# DeejBusinessCard-Top.net
KiCad netlist of a schematic drawn in Altium Designer
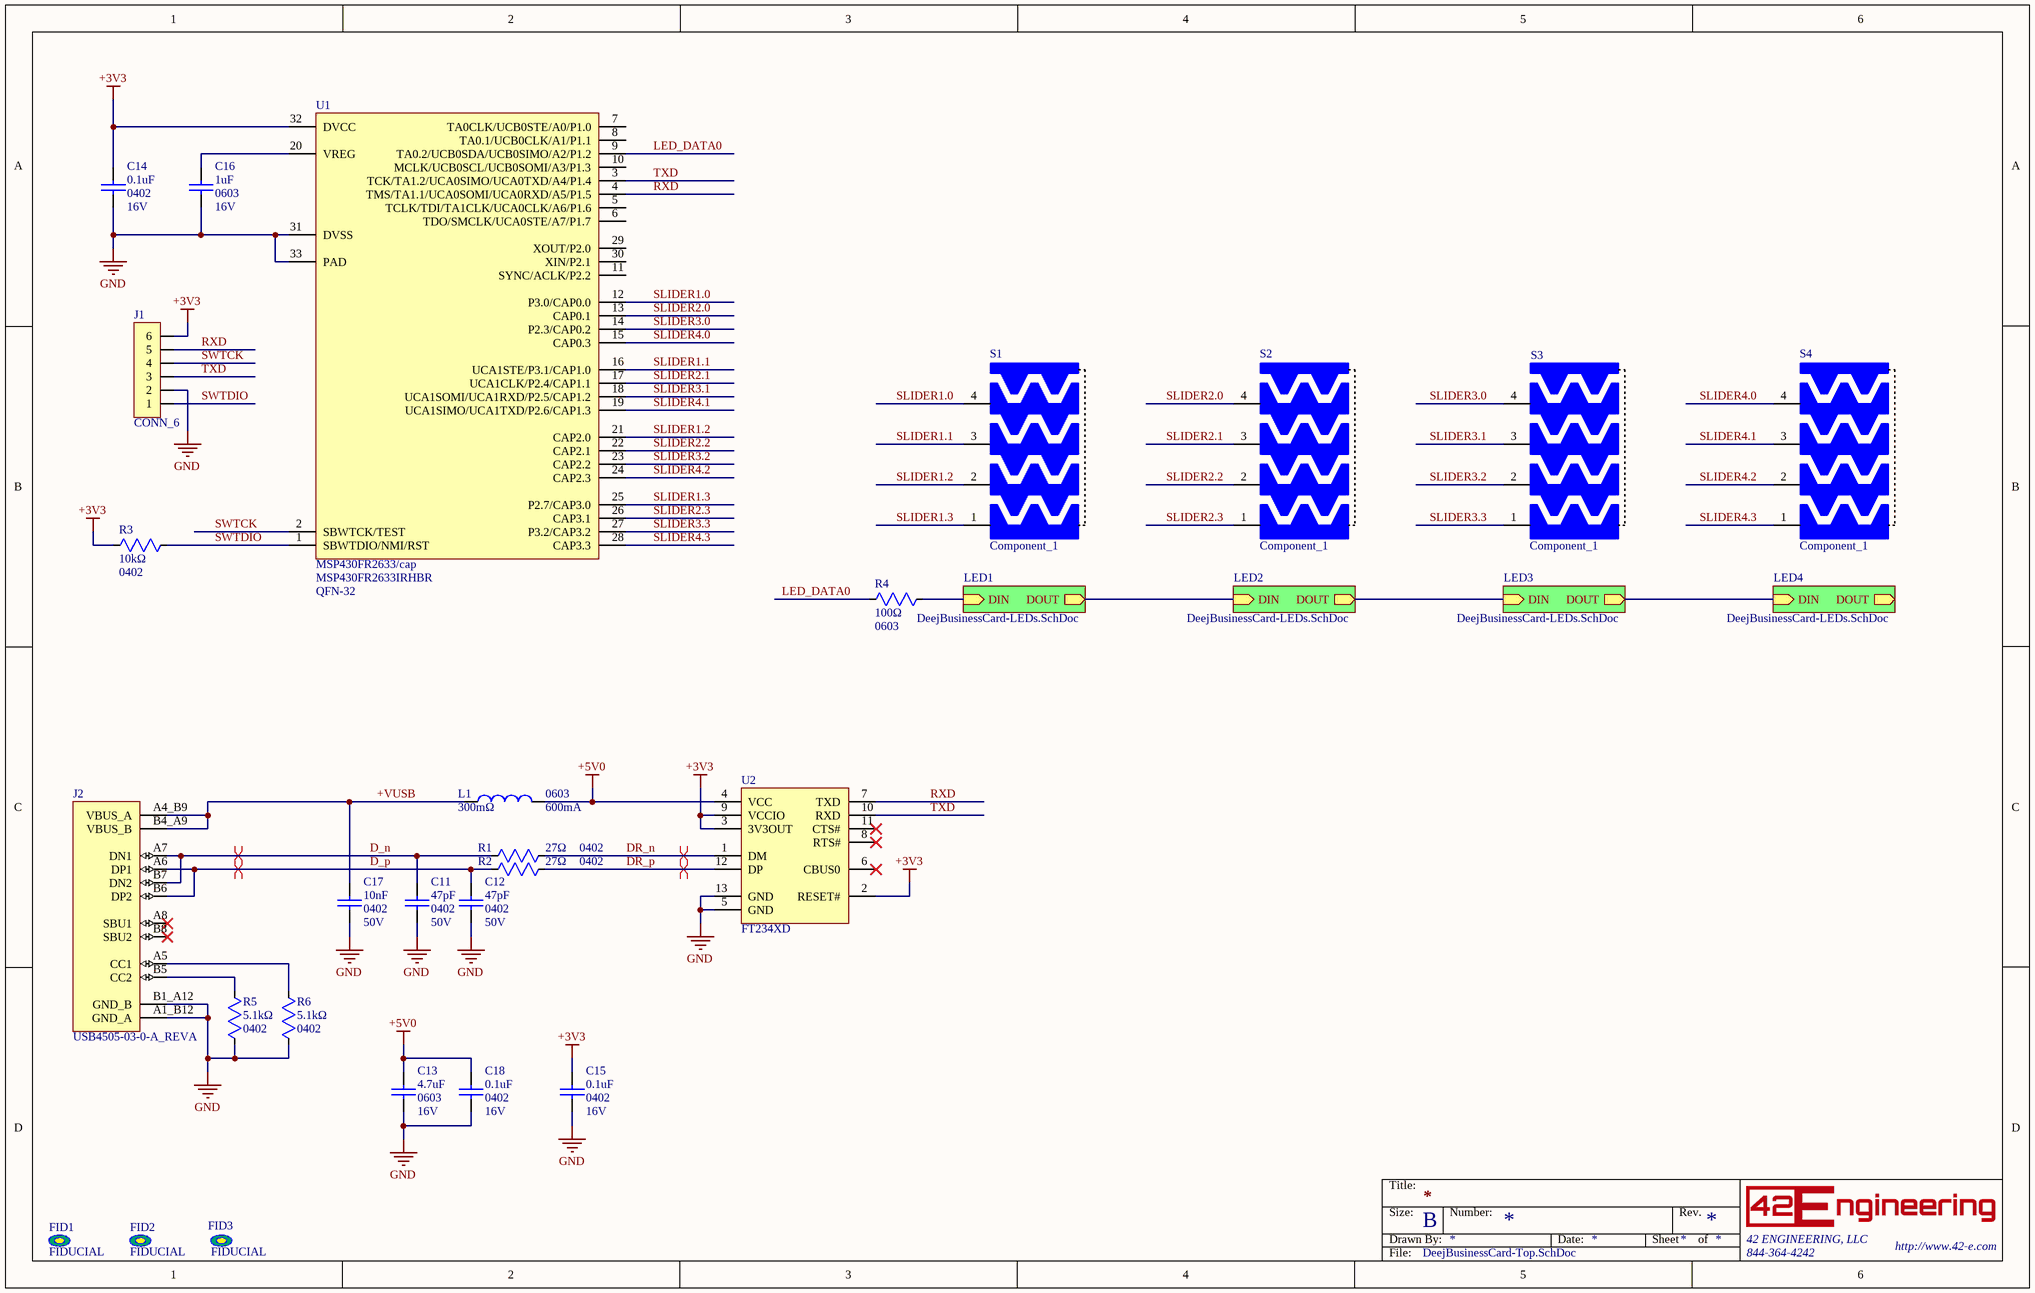
[diagram p0: DeejBusinessCard-Top.SchDoc]

(export (version "E")
  (design (tool "Eeschema 10.0.6"))
  (components
    (comp (ref "C11")
      (value "47pF")
      (footprint "CAPC1005L")
      (description "CAP CER 47PF 50V C0G/NP0 0402")
      (fields
        (field (name "CASE/PACKAGE") "0402")
        (field (name "VOLTAGE") "50V")
        (field (name "PART NUMBER") "CL05C470JB5NNNC")
        (field (name "Comment") "Capacitor_Ceramic")
      )
      (libsource (lib "Capacitors") (part "Capacitor_Ceramic"))
    )
    (comp (ref "C12")
      (value "47pF")
      (footprint "CAPC1005L")
      (description "CAP CER 47PF 50V C0G/NP0 0402")
      (fields
        (field (name "CASE/PACKAGE") "0402")
        (field (name "VOLTAGE") "50V")
        (field (name "PART NUMBER") "CL05C470JB5NNNC")
        (field (name "Comment") "Capacitor_Ceramic")
      )
      (libsource (lib "Capacitors") (part "Capacitor_Ceramic"))
    )
    (comp (ref "C13")
      (value "4.7uF")
      (footprint "CAPC1608N")
      (description "CAP CER 4.7UF 16V X7R 0603")
      (fields
        (field (name "CASE/PACKAGE") "0603")
        (field (name "VOLTAGE") "16V")
        (field (name "PART NUMBER") "GRM188Z71C475KE21J")
        (field (name "Comment") "Capacitor_Ceramic")
      )
      (libsource (lib "Capacitors") (part "Capacitor_Ceramic"))
    )
    (comp (ref "C14")
      (value "0.1uF")
      (footprint "CAPC1005L")
      (description "CAP CER 0.1UF 16V X7R 0402")
      (fields
        (field (name "CASE/PACKAGE") "0402")
        (field (name "VOLTAGE") "16V")
        (field (name "PART NUMBER") "CC0402KRX7R7BB104")
        (field (name "Comment") "Capacitor_Ceramic")
      )
      (libsource (lib "Capacitors") (part "Capacitor_Ceramic"))
    )
    (comp (ref "C15")
      (value "0.1uF")
      (footprint "CAPC1005L")
      (description "CAP CER 0.1UF 16V X7R 0402")
      (fields
        (field (name "CASE/PACKAGE") "0402")
        (field (name "VOLTAGE") "16V")
        (field (name "PART NUMBER") "CC0402KRX7R7BB104")
        (field (name "Comment") "Capacitor_Ceramic")
      )
      (libsource (lib "Capacitors") (part "Capacitor_Ceramic"))
    )
    (comp (ref "C16")
      (value "1uF")
      (footprint "CAPC1608N")
      (description "CAP CER 1UF 16V X7R 0603")
      (fields
        (field (name "CASE/PACKAGE") "0603")
        (field (name "VOLTAGE") "16V")
        (field (name "PART NUMBER") "CC0603JRX7R7BB105")
        (field (name "Comment") "Capacitor_Ceramic")
      )
      (libsource (lib "Capacitors") (part "Capacitor_Ceramic"))
    )
    (comp (ref "C17")
      (value "10nF")
      (footprint "CAPC1005L")
      (description "CAP CER 10000PF 50V X7R 0402")
      (fields
        (field (name "CASE/PACKAGE") "0402")
        (field (name "VOLTAGE") "50V")
        (field (name "PART NUMBER") "CC0402JRX7R9BB103")
        (field (name "Comment") "Capacitor_Ceramic")
      )
      (libsource (lib "Capacitors") (part "Capacitor_Ceramic"))
    )
    (comp (ref "C18")
      (value "0.1uF")
      (footprint "CAPC1005L")
      (description "CAP CER 0.1UF 16V X7R 0402")
      (fields
        (field (name "CASE/PACKAGE") "0402")
        (field (name "VOLTAGE") "16V")
        (field (name "PART NUMBER") "CC0402KRX7R7BB104")
        (field (name "Comment") "Capacitor_Ceramic")
      )
      (libsource (lib "Capacitors") (part "Capacitor_Ceramic"))
    )
    (comp (ref "FID1")
      (value "FIDUCIAL")
      (footprint "FIDUCIAL_1mm")
      (description "1MM Fiducial")
      (libsource (lib "42e-SharedLib") (part "FIDUCIAL"))
    )
    (comp (ref "FID2")
      (value "FIDUCIAL")
      (footprint "FIDUCIAL_1mm")
      (description "1MM Fiducial")
      (libsource (lib "42e-SharedLib") (part "FIDUCIAL"))
    )
    (comp (ref "FID3")
      (value "FIDUCIAL")
      (footprint "FIDUCIAL_1mm")
      (description "1MM Fiducial")
      (libsource (lib "42e-SharedLib") (part "FIDUCIAL"))
    )
    (comp (ref "J1")
      (value "CONN_6")
      (footprint "HDR - TC2030-IDC-NL-FP")
      (fields (field (name "PART NUMBER") "Header GENERIC 6pin POGO"))
      (libsource (lib "Mechanical_Other") (part "CONN_6"))
    )
    (comp (ref "J2")
      (value "USB4505-03-0-A_REVA")
      (footprint "GCT_USB4505-03-0-A_REVA")
      (fields (field (name "MP") "USB4505-03-0-A") (field (name "MF") "Global Connector Technology"))
      (libsource (lib "USB4505-03-0-A_REVA") (part "USB4505-03-0-A_REVA"))
    )
    (comp (ref "L1")
      (value "300mΩ")
      (footprint "RESC1608N")
      (description "FERRITE BEAD 1K OHM 0603 1LN")
      (fields
        (field (name "PART NUMBER") "742792662")
        (field (name "CASE/PACKAGE") "0603")
        (field (name "CURRENT") "600mA")
        (field (name "Comment") "Inductor")
      )
      (libsource (lib "Inductors") (part "Inductor"))
    )
    (comp (ref "R1")
      (value "27Ω")
      (footprint "RESC1005L")
      (description "Resistor, 27Ω, 1%, 0.05W, 0402")
      (fields
        (field (name "CASE/PACKAGE") "0402")
        (field (name "PART NUMBER") "RES0402F27R0")
        (field (name "Comment") "Resistor")
      )
      (libsource (lib "Resistors") (part "Resistor"))
    )
    (comp (ref "R2")
      (value "27Ω")
      (footprint "RESC1005L")
      (description "Resistor, 27Ω, 1%, 0.05W, 0402")
      (fields
        (field (name "CASE/PACKAGE") "0402")
        (field (name "PART NUMBER") "RES0402F27R0")
        (field (name "Comment") "Resistor")
      )
      (libsource (lib "Resistors") (part "Resistor"))
    )
    (comp (ref "R3")
      (value "10kΩ")
      (footprint "RESC1005L")
      (description "Resistor, 10kΩ, 1%, 0.05W, 0402")
      (fields
        (field (name "CASE/PACKAGE") "0402")
        (field (name "PART NUMBER") "RES0402F10K0")
        (field (name "Comment") "Resistor")
      )
      (libsource (lib "Resistors") (part "Resistor"))
    )
    (comp (ref "R4")
      (value "100Ω")
      (footprint "RESC1608N")
      (description "Resistor, 100Ω, 1%, 0.1W, 0603")
      (fields
        (field (name "CASE/PACKAGE") "0603")
        (field (name "PART NUMBER") "RES0603F100R")
        (field (name "Comment") "Resistor")
      )
      (libsource (lib "Resistors") (part "Resistor"))
    )
    (comp (ref "R5")
      (value "5.1kΩ")
      (footprint "RESC1005L")
      (description "Resistor, 5.1kΩ, 1%, 0.05W, 0402")
      (fields
        (field (name "CASE/PACKAGE") "0402")
        (field (name "PART NUMBER") "RES0402F5K10")
        (field (name "Comment") "Resistor")
      )
      (libsource (lib "Resistors") (part "Resistor"))
    )
    (comp (ref "R6")
      (value "5.1kΩ")
      (footprint "RESC1005L")
      (description "Resistor, 5.1kΩ, 1%, 0.05W, 0402")
      (fields
        (field (name "CASE/PACKAGE") "0402")
        (field (name "PART NUMBER") "RES0402F5K10")
        (field (name "Comment") "Resistor")
      )
      (libsource (lib "Resistors") (part "Resistor"))
    )
    (comp (ref "S1")
      (value "Component_1")
      (footprint "SLIDER-4-38-13")
      (libsource (lib "Schlib1") (part "Component_1"))
    )
    (comp (ref "S2")
      (value "Component_1")
      (footprint "SLIDER-4-38-13")
      (libsource (lib "Schlib1") (part "Component_1"))
    )
    (comp (ref "S3")
      (value "Component_1")
      (footprint "SLIDER-4-38-13")
      (libsource (lib "Schlib1") (part "Component_1"))
    )
    (comp (ref "S4")
      (value "Component_1")
      (footprint "SLIDER-4-38-13")
      (libsource (lib "Schlib1") (part "Component_1"))
    )
    (comp (ref "U1")
      (value "MSP430FR2633/cap")
      (footprint "QFN50P500X500X100_HS-33N")
      (description "IC MCU 16BIT 15.5KB FRAM 32VQFN")
      (fields
        (field (name "PART NUMBER") "MSP430FR2633")
        (field (name "MANUFACTURER PART NUMBER 1") "MSP430FR2633IRHBR")
        (field (name "CASE/PACKAGE") "QFN-32")
      )
      (libsource (lib "ICs") (part "MSP430FR2633/cap"))
    )
    (comp (ref "U2")
      (value "FT234XD")
      (footprint "SON45P300X80_HS-13N")
      (description "IC USB SERIAL BASIC UART 12DFN")
      (libsource (lib "UEC Shared Schematic Library") (part "FT234XD"))
    )
  )
  (nets
    (net (code "1") (name "+3V3") (class "Default")
      (node (ref "C14") (pin "1") (pinfunction "1_1") (pintype "passive"))
      (node (ref "C15") (pin "1") (pinfunction "1_1") (pintype "passive"))
      (node (ref "J1") (pin "6") (pinfunction "6_6") (pintype "passive"))
      (node (ref "R3") (pin "2") (pintype "passive"))
      (node (ref "U1") (pin "32") (pinfunction "DVCC_32") (pintype "passive"))
      (node (ref "U2") (pin "2") (pinfunction "RESET#_2") (pintype "passive"))
      (node (ref "U2") (pin "3") (pinfunction "3V3OUT_3") (pintype "passive"))
      (node (ref "U2") (pin "9") (pinfunction "VCCIO_9") (pintype "passive"))
    )
    (net (code "2") (name "+5V0") (class "Default")
      (node (ref "C13") (pin "2") (pinfunction "2_2") (pintype "passive"))
      (node (ref "C18") (pin "1") (pinfunction "1_1") (pintype "passive"))
      (node (ref "L1") (pin "2") (pinfunction "Pri-_2") (pintype "passive"))
      (node (ref "U2") (pin "4") (pinfunction "VCC_4") (pintype "passive"))
    )
    (net (code "3") (name "/+VUSB") (class "Default")
      (node (ref "C17") (pin "2") (pinfunction "2_2") (pintype "passive"))
      (node (ref "J2") (pin "A4_B9") (pinfunction "VBUS_A_A4_B9") (pintype "power_in"))
      (node (ref "J2") (pin "B4_A9") (pinfunction "VBUS_B_B4_A9") (pintype "power_in"))
      (node (ref "L1") (pin "1") (pinfunction "Pri+_1") (pintype "passive"))
    )
    (net (code "4") (name "/DIN") (class "Default") (node (ref "R4") (pin "2") (pintype "passive")))
    (net (code "9") (name "/DR_n") (class "Default")
      (node (ref "R1") (pin "2") (pintype "passive"))
      (node (ref "U2") (pin "1") (pinfunction "DM_1") (pintype "passive"))
    )
    (net (code "10") (name "/DR_p") (class "Default")
      (node (ref "R2") (pin "2") (pintype "passive"))
      (node (ref "U2") (pin "12") (pinfunction "DP_12") (pintype "passive"))
    )
    (net (code "11") (name "/D_n") (class "Default")
      (node (ref "C11") (pin "2") (pinfunction "2_2") (pintype "passive"))
      (node (ref "J2") (pin "A7") (pinfunction "DN1_A7") (pintype "bidirectional"))
      (node (ref "J2") (pin "B7") (pinfunction "DN2_B7") (pintype "bidirectional"))
      (node (ref "R1") (pin "1") (pintype "passive"))
    )
    (net (code "12") (name "/D_p") (class "Default")
      (node (ref "C12") (pin "2") (pinfunction "2_2") (pintype "passive"))
      (node (ref "J2") (pin "A6") (pinfunction "DP1_A6") (pintype "bidirectional"))
      (node (ref "J2") (pin "B6") (pinfunction "DP2_B6") (pintype "bidirectional"))
      (node (ref "R2") (pin "1") (pintype "passive"))
    )
    (net (code "13") (name "/LED_DATA0") (class "Default")
      (node (ref "R4") (pin "1") (pintype "passive"))
      (node (ref "U1") (pin "9") (pinfunction "TA0.2/UCB0SDA/UCB0SIMO/A2/P1.2_9") (pintype "passive"))
    )
    (net (code "14") (name "/RXD") (class "Default")
      (node (ref "J1") (pin "5") (pinfunction "5_5") (pintype "passive"))
      (node (ref "U1") (pin "4") (pinfunction "TMS/TA1.1/UCA0SOMI/UCA0RXD/A5/P1.5_4") (pintype "passive"))
      (node (ref "U2") (pin "7") (pinfunction "TXD_7") (pintype "passive"))
    )
    (net (code "15") (name "/SLIDER1.0") (class "Default")
      (node (ref "S1") (pin "4") (pinfunction "4_4") (pintype "passive"))
      (node (ref "U1") (pin "12") (pinfunction "P3.0/CAP0.0_12") (pintype "passive"))
    )
    (net (code "16") (name "/SLIDER1.1") (class "Default")
      (node (ref "S1") (pin "3") (pinfunction "3_3") (pintype "passive"))
      (node (ref "U1") (pin "16") (pinfunction "UCA1STE/P3.1/CAP1.0_16") (pintype "passive"))
    )
    (net (code "17") (name "/SLIDER1.2") (class "Default")
      (node (ref "S1") (pin "2") (pinfunction "2_2") (pintype "passive"))
      (node (ref "U1") (pin "21") (pinfunction "CAP2.0_21") (pintype "passive"))
    )
    (net (code "18") (name "/SLIDER1.3") (class "Default")
      (node (ref "S1") (pin "1") (pinfunction "1_1") (pintype "passive"))
      (node (ref "U1") (pin "25") (pinfunction "P2.7/CAP3.0_25") (pintype "passive"))
    )
    (net (code "19") (name "/SLIDER2.0") (class "Default")
      (node (ref "S2") (pin "4") (pinfunction "4_4") (pintype "passive"))
      (node (ref "U1") (pin "13") (pinfunction "CAP0.1_13") (pintype "passive"))
    )
    (net (code "20") (name "/SLIDER2.1") (class "Default")
      (node (ref "S2") (pin "3") (pinfunction "3_3") (pintype "passive"))
      (node (ref "U1") (pin "17") (pinfunction "UCA1CLK/P2.4/CAP1.1_17") (pintype "passive"))
    )
    (net (code "21") (name "/SLIDER2.2") (class "Default")
      (node (ref "S2") (pin "2") (pinfunction "2_2") (pintype "passive"))
      (node (ref "U1") (pin "22") (pinfunction "CAP2.1_22") (pintype "passive"))
    )
    (net (code "22") (name "/SLIDER2.3") (class "Default")
      (node (ref "S2") (pin "1") (pinfunction "1_1") (pintype "passive"))
      (node (ref "U1") (pin "26") (pinfunction "CAP3.1_26") (pintype "passive"))
    )
    (net (code "23") (name "/SLIDER3.0") (class "Default")
      (node (ref "S3") (pin "4") (pinfunction "4_4") (pintype "passive"))
      (node (ref "U1") (pin "14") (pinfunction "P2.3/CAP0.2_14") (pintype "passive"))
    )
    (net (code "24") (name "/SLIDER3.1") (class "Default")
      (node (ref "S3") (pin "3") (pinfunction "3_3") (pintype "passive"))
      (node (ref "U1") (pin "18") (pinfunction "UCA1SOMI/UCA1RXD/P2.5/CAP1.2_18") (pintype "passive"))
    )
    (net (code "25") (name "/SLIDER3.2") (class "Default")
      (node (ref "S3") (pin "2") (pinfunction "2_2") (pintype "passive"))
      (node (ref "U1") (pin "23") (pinfunction "CAP2.2_23") (pintype "passive"))
    )
    (net (code "26") (name "/SLIDER3.3") (class "Default")
      (node (ref "S3") (pin "1") (pinfunction "1_1") (pintype "passive"))
      (node (ref "U1") (pin "27") (pinfunction "P3.2/CAP3.2_27") (pintype "passive"))
    )
    (net (code "27") (name "/SLIDER4.0") (class "Default")
      (node (ref "S4") (pin "4") (pinfunction "4_4") (pintype "passive"))
      (node (ref "U1") (pin "15") (pinfunction "CAP0.3_15") (pintype "passive"))
    )
    (net (code "28") (name "/SLIDER4.1") (class "Default")
      (node (ref "S4") (pin "3") (pinfunction "3_3") (pintype "passive"))
      (node (ref "U1") (pin "19") (pinfunction "UCA1SIMO/UCA1TXD/P2.6/CAP1.3_19") (pintype "passive"))
    )
    (net (code "29") (name "/SLIDER4.2") (class "Default")
      (node (ref "S4") (pin "2") (pinfunction "2_2") (pintype "passive"))
      (node (ref "U1") (pin "24") (pinfunction "CAP2.3_24") (pintype "passive"))
    )
    (net (code "30") (name "/SLIDER4.3") (class "Default")
      (node (ref "S4") (pin "1") (pinfunction "1_1") (pintype "passive"))
      (node (ref "U1") (pin "28") (pinfunction "CAP3.3_28") (pintype "passive"))
    )
    (net (code "31") (name "/SWTCK") (class "Default")
      (node (ref "J1") (pin "4") (pinfunction "4_4") (pintype "passive"))
      (node (ref "U1") (pin "2") (pinfunction "SBWTCK/TEST_2") (pintype "passive"))
    )
    (net (code "32") (name "/SWTDIO") (class "Default")
      (node (ref "J1") (pin "1") (pinfunction "1_1") (pintype "passive"))
      (node (ref "R3") (pin "1") (pintype "passive"))
      (node (ref "U1") (pin "1") (pinfunction "SBWTDIO/NMI/RST_1") (pintype "passive"))
    )
    (net (code "33") (name "/TXD") (class "Default")
      (node (ref "J1") (pin "3") (pinfunction "3_3") (pintype "passive"))
      (node (ref "U1") (pin "3") (pinfunction "TCK/TA1.2/UCA0SIMO/UCA0TXD/A4/P1.4_3") (pintype "passive"))
      (node (ref "U2") (pin "10") (pinfunction "RXD_10") (pintype "passive"))
    )
    (net (code "34") (name "GND") (class "Default")
      (node (ref "C11") (pin "1") (pinfunction "1_1") (pintype "passive"))
      (node (ref "C12") (pin "1") (pinfunction "1_1") (pintype "passive"))
      (node (ref "C13") (pin "1") (pinfunction "1_1") (pintype "passive"))
      (node (ref "C14") (pin "2") (pinfunction "2_2") (pintype "passive"))
      (node (ref "C15") (pin "2") (pinfunction "2_2") (pintype "passive"))
      (node (ref "C16") (pin "1") (pinfunction "1_1") (pintype "passive"))
      (node (ref "C17") (pin "1") (pinfunction "1_1") (pintype "passive"))
      (node (ref "C18") (pin "2") (pinfunction "2_2") (pintype "passive"))
      (node (ref "J1") (pin "2") (pinfunction "2_2") (pintype "passive"))
      (node (ref "J2") (pin "A1_B12") (pinfunction "GND_A_A1_B12") (pintype "power_in"))
      (node (ref "J2") (pin "B1_A12") (pinfunction "GND_B_B1_A12") (pintype "power_in"))
      (node (ref "R5") (pin "1") (pintype "passive"))
      (node (ref "R6") (pin "1") (pintype "passive"))
      (node (ref "U1") (pin "31") (pinfunction "DVSS_31") (pintype "passive"))
      (node (ref "U1") (pin "33") (pinfunction "PAD_33") (pintype "passive"))
      (node (ref "U2") (pin "13") (pinfunction "GND_13") (pintype "passive"))
      (node (ref "U2") (pin "5") (pinfunction "GND_5") (pintype "passive"))
    )
    (net (code "35") (name "Net-(J2-CC1)") (class "Default")
      (node (ref "J2") (pin "A5") (pinfunction "CC1_A5") (pintype "bidirectional"))
      (node (ref "R6") (pin "2") (pintype "passive"))
    )
    (net (code "36") (name "Net-(J2-CC2)") (class "Default")
      (node (ref "J2") (pin "B5") (pinfunction "CC2_B5") (pintype "bidirectional"))
      (node (ref "R5") (pin "2") (pintype "passive"))
    )
    (net (code "37") (name "Net-(U1-VREG)") (class "Default")
      (node (ref "C16") (pin "2") (pinfunction "2_2") (pintype "passive"))
      (node (ref "U1") (pin "20") (pinfunction "VREG_20") (pintype "passive"))
    )
    (net (code "38") (name "unconnected-(J2-SBU1-PadA8)") (class "Default")
      (node (ref "J2") (pin "A8") (pinfunction "SBU1_A8") (pintype "bidirectional+no_connect"))
    )
    (net (code "39") (name "unconnected-(J2-SBU2-PadB8)") (class "Default")
      (node (ref "J2") (pin "B8") (pinfunction "SBU2_B8") (pintype "bidirectional+no_connect"))
    )
    (net (code "40") (name "unconnected-(U1-MCLK{slash}UCB0SCL{slash}UCB0SOMI{slash}A3{slash}P1.3-Pad10)") (class "Default")
      (node (ref "U1") (pin "10") (pinfunction "MCLK/UCB0SCL/UCB0SOMI/A3/P1.3_10") (pintype "passive"))
    )
    (net (code "41") (name "unconnected-(U1-SYNC{slash}ACLK{slash}P2.2-Pad11)") (class "Default")
      (node (ref "U1") (pin "11") (pinfunction "SYNC/ACLK/P2.2_11") (pintype "passive"))
    )
    (net (code "42") (name "unconnected-(U1-TA0.1{slash}UCB0CLK{slash}A1{slash}P1.1-Pad8)") (class "Default")
      (node (ref "U1") (pin "8") (pinfunction "TA0.1/UCB0CLK/A1/P1.1_8") (pintype "passive"))
    )
    (net (code "43") (name "unconnected-(U1-TA0CLK{slash}UCB0STE{slash}A0{slash}P1.0-Pad7)") (class "Default")
      (node (ref "U1") (pin "7") (pinfunction "TA0CLK/UCB0STE/A0/P1.0_7") (pintype "passive"))
    )
    (net (code "44") (name "unconnected-(U1-TCLK{slash}TDI{slash}TA1CLK{slash}UCA0CLK{slash}A6{slash}P1.6-Pad5)") (class "Default")
      (node (ref "U1") (pin "5") (pinfunction "TCLK/TDI/TA1CLK/UCA0CLK/A6/P1.6_5") (pintype "passive"))
    )
    (net (code "45") (name "unconnected-(U1-TDO{slash}SMCLK{slash}UCA0STE{slash}A7{slash}P1.7-Pad6)") (class "Default")
      (node (ref "U1") (pin "6") (pinfunction "TDO/SMCLK/UCA0STE/A7/P1.7_6") (pintype "passive"))
    )
    (net (code "46") (name "unconnected-(U1-XIN{slash}P2.1-Pad30)") (class "Default")
      (node (ref "U1") (pin "30") (pinfunction "XIN/P2.1_30") (pintype "passive"))
    )
    (net (code "47") (name "unconnected-(U1-XOUT{slash}P2.0-Pad29)") (class "Default")
      (node (ref "U1") (pin "29") (pinfunction "XOUT/P2.0_29") (pintype "passive"))
    )
    (net (code "48") (name "unconnected-(U2-CBUS0-Pad6)") (class "Default")
      (node (ref "U2") (pin "6") (pinfunction "CBUS0_6") (pintype "passive+no_connect"))
    )
    (net (code "49") (name "unconnected-(U2-CTS#-Pad11)") (class "Default")
      (node (ref "U2") (pin "11") (pinfunction "CTS#_11") (pintype "passive+no_connect"))
    )
    (net (code "50") (name "unconnected-(U2-RTS#-Pad8)") (class "Default")
      (node (ref "U2") (pin "8") (pinfunction "RTS#_8") (pintype "passive+no_connect"))
    )
  )
)
